# LED.net
KiCad netlist of a schematic drawn in Altium Designer
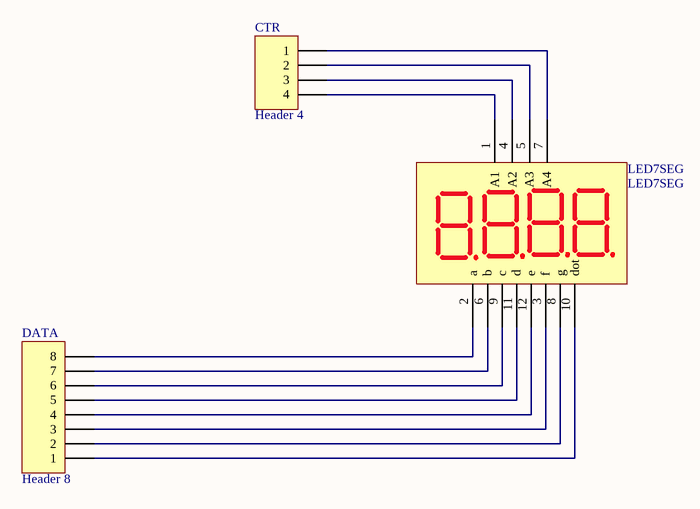
[diagram p0: LED.SchDoc]

(export (version "E")
  (design (tool "Eeschema 10.0.6"))
  (components
    (comp (ref "CTR")
      (value "Header 4")
      (footprint "Device:CAP 4")
      (description "Header, 4-Pin")
      (fields (field (name "PUBLISHER") "Altium Limited"))
      (libsource (lib "Miscellaneous Connectors") (part "Header 4"))
    )
    (comp (ref "DATA")
      (value "Header 8")
      (footprint "Device:Cap_8")
      (description "Header, 8-Pin")
      (fields (field (name "PUBLISHER") "Altium Limited"))
      (libsource (lib "Miscellaneous Connectors") (part "Header 8"))
    )
    (comp (ref "LED7SEG")
      (value "LED7SEG")
      (footprint "Device:LED7SEGMENT_4")
      (libsource (lib "Device_Component") (part "LED7SEG"))
    )
  )
  (nets
    (net (code "1") (name "Net-(LED7SEG-A1)") (class "Default")
      (node (ref "CTR") (pin "4") (pinfunction "4_4") (pintype "passive"))
      (node (ref "LED7SEG") (pin "1") (pinfunction "A1_1") (pintype "passive"))
    )
    (net (code "2") (name "Net-(LED7SEG-A2)") (class "Default")
      (node (ref "CTR") (pin "3") (pinfunction "3_3") (pintype "passive"))
      (node (ref "LED7SEG") (pin "4") (pinfunction "A2_4") (pintype "passive"))
    )
    (net (code "3") (name "Net-(LED7SEG-A3)") (class "Default")
      (node (ref "CTR") (pin "2") (pinfunction "2_2") (pintype "passive"))
      (node (ref "LED7SEG") (pin "5") (pinfunction "A3_5") (pintype "passive"))
    )
    (net (code "4") (name "Net-(LED7SEG-A4)") (class "Default")
      (node (ref "CTR") (pin "1") (pinfunction "1_1") (pintype "passive"))
      (node (ref "LED7SEG") (pin "7") (pinfunction "A4_7") (pintype "passive"))
    )
    (net (code "5") (name "Net-(LED7SEG-a)") (class "Default")
      (node (ref "DATA") (pin "8") (pinfunction "8_8") (pintype "passive"))
      (node (ref "LED7SEG") (pin "2") (pinfunction "a_2") (pintype "passive"))
    )
    (net (code "6") (name "Net-(LED7SEG-b)") (class "Default")
      (node (ref "DATA") (pin "7") (pinfunction "7_7") (pintype "passive"))
      (node (ref "LED7SEG") (pin "6") (pinfunction "b_6") (pintype "passive"))
    )
    (net (code "7") (name "Net-(LED7SEG-c)") (class "Default")
      (node (ref "DATA") (pin "6") (pinfunction "6_6") (pintype "passive"))
      (node (ref "LED7SEG") (pin "9") (pinfunction "c_9") (pintype "passive"))
    )
    (net (code "8") (name "Net-(LED7SEG-d)") (class "Default")
      (node (ref "DATA") (pin "5") (pinfunction "5_5") (pintype "passive"))
      (node (ref "LED7SEG") (pin "11") (pinfunction "d_11") (pintype "passive"))
    )
    (net (code "9") (name "Net-(LED7SEG-dot)") (class "Default")
      (node (ref "DATA") (pin "1") (pinfunction "1_1") (pintype "passive"))
      (node (ref "LED7SEG") (pin "10") (pinfunction "dot_10") (pintype "passive"))
    )
    (net (code "10") (name "Net-(LED7SEG-e)") (class "Default")
      (node (ref "DATA") (pin "4") (pinfunction "4_4") (pintype "passive"))
      (node (ref "LED7SEG") (pin "12") (pinfunction "e_12") (pintype "passive"))
    )
    (net (code "11") (name "Net-(LED7SEG-f)") (class "Default")
      (node (ref "DATA") (pin "3") (pinfunction "3_3") (pintype "passive"))
      (node (ref "LED7SEG") (pin "3") (pinfunction "f_3") (pintype "passive"))
    )
    (net (code "12") (name "Net-(LED7SEG-g)") (class "Default")
      (node (ref "DATA") (pin "2") (pinfunction "2_2") (pintype "passive"))
      (node (ref "LED7SEG") (pin "8") (pinfunction "g_8") (pintype "passive"))
    )
  )
)
